# Felderblock_Hebelplatine.net
KiCad netlist of a schematic drawn in EAGLE
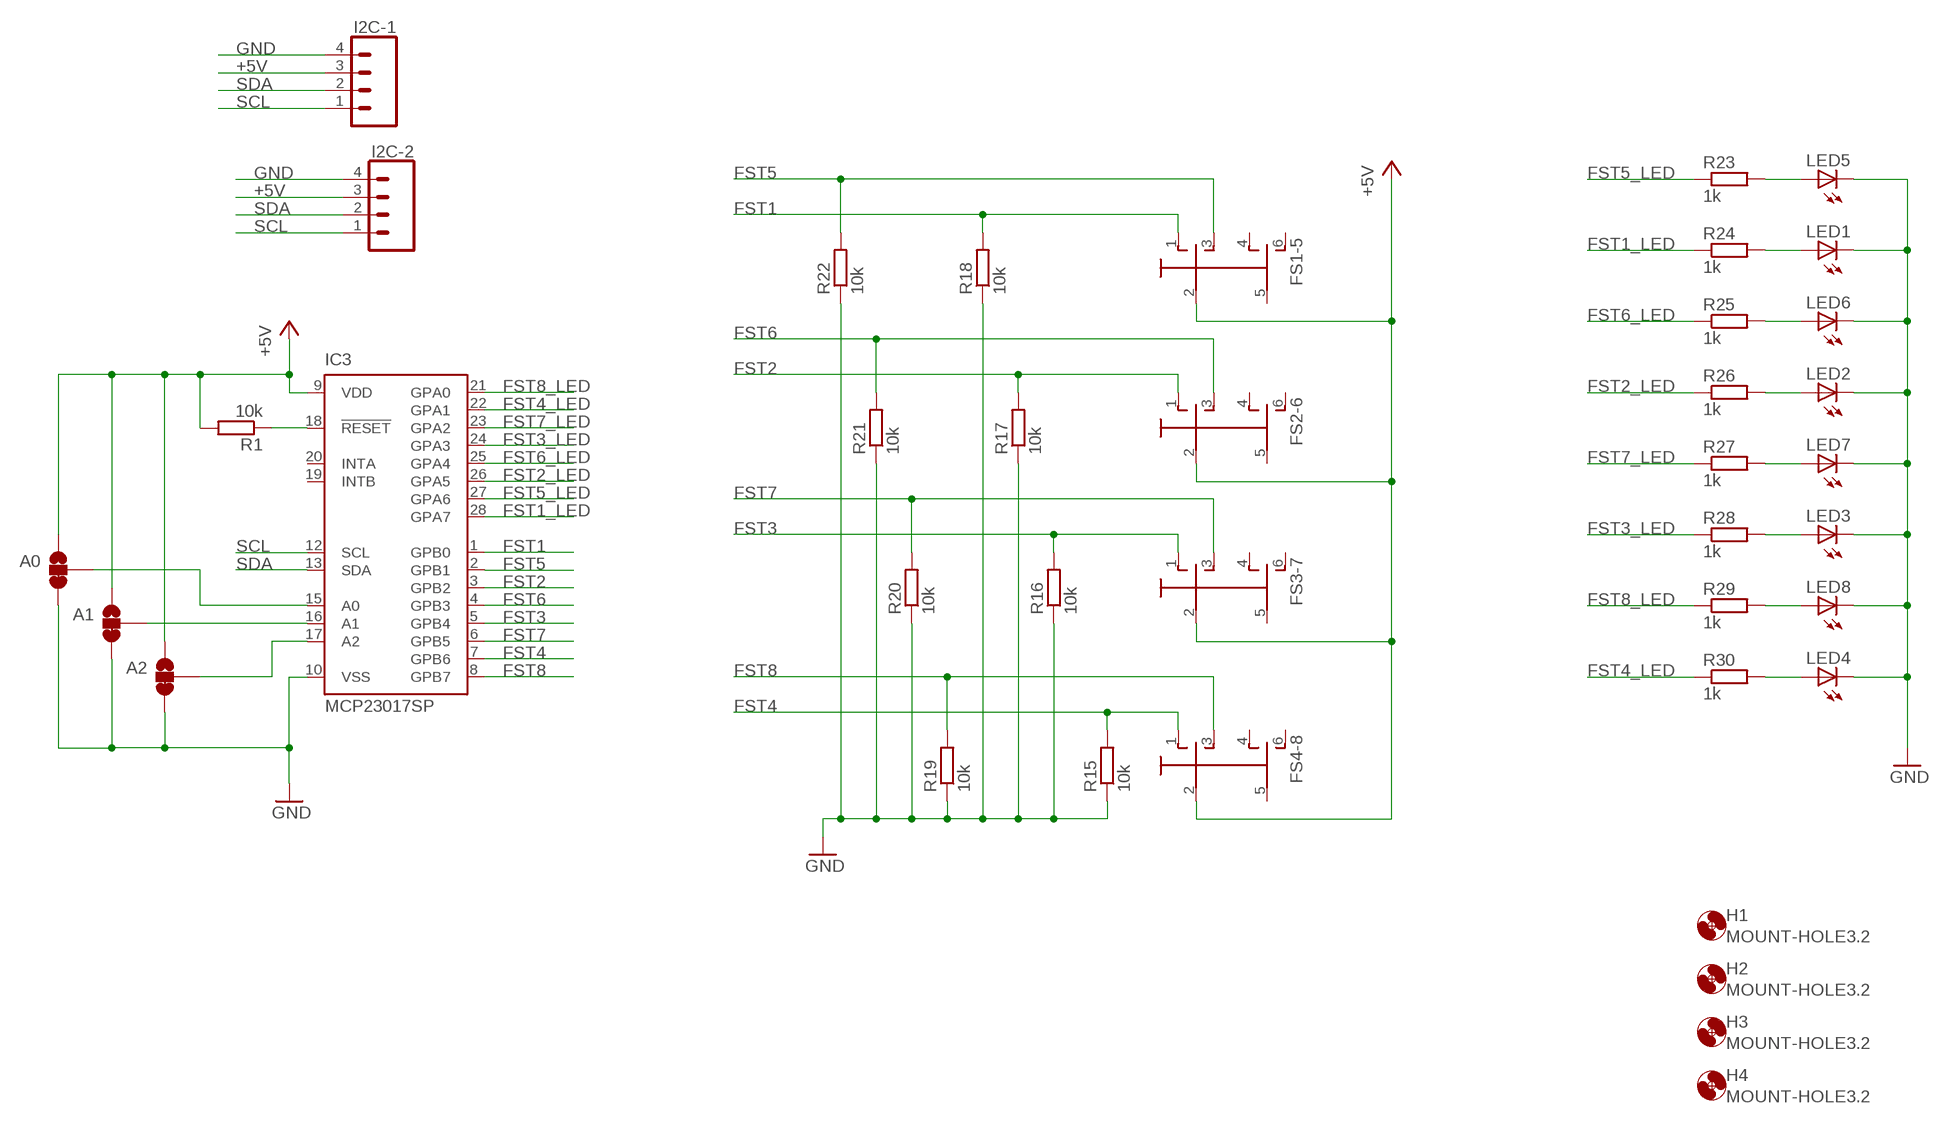
[diagram p0: schematic, sheet 1]

(export (version "E")
  (design (tool "Eeschema 10.0.6"))
  (components
    (comp (ref "A0")
      (value "JUMPER-SMT_3_1-NC_TRACE_SILK")
      (footprint "eagle-import:SMT-JUMPER_3_1-NC_TRACE_SILK")
      (libsource (lib "eagle-import") (part "JUMPER-SMT_3_1-NC_TRACE_SILK"))
    )
    (comp (ref "A1")
      (value "JUMPER-SMT_3_1-NC_TRACE_SILK")
      (footprint "eagle-import:SMT-JUMPER_3_1-NC_TRACE_SILK")
      (libsource (lib "eagle-import") (part "JUMPER-SMT_3_1-NC_TRACE_SILK"))
    )
    (comp (ref "A2")
      (value "JUMPER-SMT_3_1-NC_TRACE_SILK")
      (footprint "eagle-import:SMT-JUMPER_3_1-NC_TRACE_SILK")
      (libsource (lib "eagle-import") (part "JUMPER-SMT_3_1-NC_TRACE_SILK"))
    )
    (comp (ref "FS1-5")
      (value "SW_2POL_ON-OFF-ONSOLDERPAD")
      (footprint "eagle-import:DIL6_LARGE")
      (libsource (lib "eagle-import") (part "SW_2POL_ON-OFF-ONSOLDERPAD"))
    )
    (comp (ref "FS2-6")
      (value "SW_2POL_ON-OFF-ONSOLDERPAD")
      (footprint "eagle-import:DIL6_LARGE")
      (libsource (lib "eagle-import") (part "SW_2POL_ON-OFF-ONSOLDERPAD"))
    )
    (comp (ref "FS3-7")
      (value "SW_2POL_ON-OFF-ONSOLDERPAD")
      (footprint "eagle-import:DIL6_LARGE")
      (libsource (lib "eagle-import") (part "SW_2POL_ON-OFF-ONSOLDERPAD"))
    )
    (comp (ref "FS4-8")
      (value "SW_2POL_ON-OFF-ONSOLDERPAD")
      (footprint "eagle-import:DIL6_LARGE")
      (libsource (lib "eagle-import") (part "SW_2POL_ON-OFF-ONSOLDERPAD"))
    )
    (comp (ref "H1")
      (value "MOUNT-HOLE3.2")
      (footprint "eagle-import:3,2")
      (libsource (lib "eagle-import") (part "MOUNT-HOLE3.2"))
    )
    (comp (ref "H2")
      (value "MOUNT-HOLE3.2")
      (footprint "eagle-import:3,2")
      (libsource (lib "eagle-import") (part "MOUNT-HOLE3.2"))
    )
    (comp (ref "H3")
      (value "MOUNT-HOLE3.2")
      (footprint "eagle-import:3,2")
      (libsource (lib "eagle-import") (part "MOUNT-HOLE3.2"))
    )
    (comp (ref "H4")
      (value "MOUNT-HOLE3.2")
      (footprint "eagle-import:3,2")
      (libsource (lib "eagle-import") (part "MOUNT-HOLE3.2"))
    )
    (comp (ref "I2C-1")
      (value "CONN_04JST-PTH-VERT")
      (footprint "eagle-import:JST-4-PTH-VERT")
      (libsource (lib "eagle-import") (part "CONN_04JST-PTH-VERT"))
    )
    (comp (ref "I2C-2")
      (value "CONN_04JST-PTH-VERT")
      (footprint "eagle-import:JST-4-PTH-VERT")
      (libsource (lib "eagle-import") (part "CONN_04JST-PTH-VERT"))
    )
    (comp (ref "IC3")
      (value "MCP23017SP")
      (footprint "eagle-import:DIL28-3")
      (fields (field (name "MF") "MICROCHIP") (field (name "MPN") "MCP23017-E/SP"))
      (libsource (lib "eagle-import") (part "MCP23017SP"))
    )
    (comp (ref "LED1")
      (value "LED3MM")
      (footprint "eagle-import:LED3MM")
      (libsource (lib "eagle-import") (part "LED3MM"))
    )
    (comp (ref "LED2")
      (value "LED3MM")
      (footprint "eagle-import:LED3MM")
      (libsource (lib "eagle-import") (part "LED3MM"))
    )
    (comp (ref "LED3")
      (value "LED3MM")
      (footprint "eagle-import:LED3MM")
      (libsource (lib "eagle-import") (part "LED3MM"))
    )
    (comp (ref "LED4")
      (value "LED3MM")
      (footprint "eagle-import:LED3MM")
      (libsource (lib "eagle-import") (part "LED3MM"))
    )
    (comp (ref "LED5")
      (value "LED3MM")
      (footprint "eagle-import:LED3MM")
      (libsource (lib "eagle-import") (part "LED3MM"))
    )
    (comp (ref "LED6")
      (value "LED3MM")
      (footprint "eagle-import:LED3MM")
      (libsource (lib "eagle-import") (part "LED3MM"))
    )
    (comp (ref "LED7")
      (value "LED3MM")
      (footprint "eagle-import:LED3MM")
      (libsource (lib "eagle-import") (part "LED3MM"))
    )
    (comp (ref "LED8")
      (value "LED3MM")
      (footprint "eagle-import:LED3MM")
      (libsource (lib "eagle-import") (part "LED3MM"))
    )
    (comp (ref "R1")
      (value "10k")
      (footprint "eagle-import:0207_7")
      (libsource (lib "eagle-import") (part "R-EU_0207/7"))
    )
    (comp (ref "R15")
      (value "10k")
      (footprint "eagle-import:0207_7")
      (libsource (lib "eagle-import") (part "R-EU_0207/7"))
    )
    (comp (ref "R16")
      (value "10k")
      (footprint "eagle-import:0207_7")
      (libsource (lib "eagle-import") (part "R-EU_0207/7"))
    )
    (comp (ref "R17")
      (value "10k")
      (footprint "eagle-import:0207_7")
      (libsource (lib "eagle-import") (part "R-EU_0207/7"))
    )
    (comp (ref "R18")
      (value "10k")
      (footprint "eagle-import:0207_7")
      (libsource (lib "eagle-import") (part "R-EU_0207/7"))
    )
    (comp (ref "R19")
      (value "10k")
      (footprint "eagle-import:0207_7")
      (libsource (lib "eagle-import") (part "R-EU_0207/7"))
    )
    (comp (ref "R20")
      (value "10k")
      (footprint "eagle-import:0207_7")
      (libsource (lib "eagle-import") (part "R-EU_0207/7"))
    )
    (comp (ref "R21")
      (value "10k")
      (footprint "eagle-import:0207_7")
      (libsource (lib "eagle-import") (part "R-EU_0207/7"))
    )
    (comp (ref "R22")
      (value "10k")
      (footprint "eagle-import:0207_7")
      (libsource (lib "eagle-import") (part "R-EU_0207/7"))
    )
    (comp (ref "R23")
      (value "1k")
      (footprint "eagle-import:0207_7")
      (libsource (lib "eagle-import") (part "R-EU_0207/7"))
    )
    (comp (ref "R24")
      (value "1k")
      (footprint "eagle-import:0207_7")
      (libsource (lib "eagle-import") (part "R-EU_0207/7"))
    )
    (comp (ref "R25")
      (value "1k")
      (footprint "eagle-import:0207_7")
      (libsource (lib "eagle-import") (part "R-EU_0207/7"))
    )
    (comp (ref "R26")
      (value "1k")
      (footprint "eagle-import:0207_7")
      (libsource (lib "eagle-import") (part "R-EU_0207/7"))
    )
    (comp (ref "R27")
      (value "1k")
      (footprint "eagle-import:0207_7")
      (libsource (lib "eagle-import") (part "R-EU_0207/7"))
    )
    (comp (ref "R28")
      (value "1k")
      (footprint "eagle-import:0207_7")
      (libsource (lib "eagle-import") (part "R-EU_0207/7"))
    )
    (comp (ref "R29")
      (value "1k")
      (footprint "eagle-import:0207_7")
      (libsource (lib "eagle-import") (part "R-EU_0207/7"))
    )
    (comp (ref "R30")
      (value "1k")
      (footprint "eagle-import:0207_7")
      (libsource (lib "eagle-import") (part "R-EU_0207/7"))
    )
  )
  (nets
    (net (code "1") (name "+5V") (class "Default")
      (node (ref "A0") (pin "1") (pinfunction "1_1") (pintype "passive"))
      (node (ref "A1") (pin "1") (pinfunction "1_1") (pintype "passive"))
      (node (ref "A2") (pin "1") (pinfunction "1_1") (pintype "passive"))
      (node (ref "FS1-5") (pin "2") (pinfunction "P_2") (pintype "passive"))
      (node (ref "FS2-6") (pin "2") (pinfunction "P_2") (pintype "passive"))
      (node (ref "FS3-7") (pin "2") (pinfunction "P_2") (pintype "passive"))
      (node (ref "FS4-8") (pin "2") (pinfunction "P_2") (pintype "passive"))
      (node (ref "I2C-1") (pin "3") (pinfunction "3_3") (pintype "passive"))
      (node (ref "I2C-2") (pin "3") (pinfunction "3_3") (pintype "passive"))
      (node (ref "IC3") (pin "9") (pinfunction "VDD_9") (pintype "power_in"))
      (node (ref "R1") (pin "2") (pinfunction "2_2") (pintype "passive"))
    )
    (net (code "2") (name "/FST1") (class "Default")
      (node (ref "FS1-5") (pin "1") (pinfunction "O_1") (pintype "passive"))
      (node (ref "IC3") (pin "1") (pinfunction "GPB0_1") (pintype "bidirectional"))
      (node (ref "R18") (pin "2") (pinfunction "2_2") (pintype "passive"))
    )
    (net (code "3") (name "/FST1_LED") (class "Default")
      (node (ref "IC3") (pin "28") (pinfunction "GPA7_28") (pintype "bidirectional"))
      (node (ref "R24") (pin "1") (pinfunction "1_1") (pintype "passive"))
    )
    (net (code "4") (name "/FST2") (class "Default")
      (node (ref "FS2-6") (pin "1") (pinfunction "O_1") (pintype "passive"))
      (node (ref "IC3") (pin "3") (pinfunction "GPB2_3") (pintype "bidirectional"))
      (node (ref "R17") (pin "2") (pinfunction "2_2") (pintype "passive"))
    )
    (net (code "5") (name "/FST2_LED") (class "Default")
      (node (ref "IC3") (pin "26") (pinfunction "GPA5_26") (pintype "bidirectional"))
      (node (ref "R26") (pin "1") (pinfunction "1_1") (pintype "passive"))
    )
    (net (code "6") (name "/FST3") (class "Default")
      (node (ref "FS3-7") (pin "1") (pinfunction "O_1") (pintype "passive"))
      (node (ref "IC3") (pin "5") (pinfunction "GPB4_5") (pintype "bidirectional"))
      (node (ref "R16") (pin "2") (pinfunction "2_2") (pintype "passive"))
    )
    (net (code "7") (name "/FST3_LED") (class "Default")
      (node (ref "IC3") (pin "24") (pinfunction "GPA3_24") (pintype "bidirectional"))
      (node (ref "R28") (pin "1") (pinfunction "1_1") (pintype "passive"))
    )
    (net (code "8") (name "/FST4") (class "Default")
      (node (ref "FS4-8") (pin "1") (pinfunction "O_1") (pintype "passive"))
      (node (ref "IC3") (pin "7") (pinfunction "GPB6_7") (pintype "bidirectional"))
      (node (ref "R15") (pin "2") (pinfunction "2_2") (pintype "passive"))
    )
    (net (code "9") (name "/FST4_LED") (class "Default")
      (node (ref "IC3") (pin "22") (pinfunction "GPA1_22") (pintype "bidirectional"))
      (node (ref "R30") (pin "1") (pinfunction "1_1") (pintype "passive"))
    )
    (net (code "10") (name "/FST5") (class "Default")
      (node (ref "FS1-5") (pin "3") (pinfunction "S_3") (pintype "passive"))
      (node (ref "IC3") (pin "2") (pinfunction "GPB1_2") (pintype "bidirectional"))
      (node (ref "R22") (pin "2") (pinfunction "2_2") (pintype "passive"))
    )
    (net (code "11") (name "/FST5_LED") (class "Default")
      (node (ref "IC3") (pin "27") (pinfunction "GPA6_27") (pintype "bidirectional"))
      (node (ref "R23") (pin "1") (pinfunction "1_1") (pintype "passive"))
    )
    (net (code "12") (name "/FST6") (class "Default")
      (node (ref "FS2-6") (pin "3") (pinfunction "S_3") (pintype "passive"))
      (node (ref "IC3") (pin "4") (pinfunction "GPB3_4") (pintype "bidirectional"))
      (node (ref "R21") (pin "2") (pinfunction "2_2") (pintype "passive"))
    )
    (net (code "13") (name "/FST6_LED") (class "Default")
      (node (ref "IC3") (pin "25") (pinfunction "GPA4_25") (pintype "bidirectional"))
      (node (ref "R25") (pin "1") (pinfunction "1_1") (pintype "passive"))
    )
    (net (code "14") (name "/FST7") (class "Default")
      (node (ref "FS3-7") (pin "3") (pinfunction "S_3") (pintype "passive"))
      (node (ref "IC3") (pin "6") (pinfunction "GPB5_6") (pintype "bidirectional"))
      (node (ref "R20") (pin "2") (pinfunction "2_2") (pintype "passive"))
    )
    (net (code "15") (name "/FST7_LED") (class "Default")
      (node (ref "IC3") (pin "23") (pinfunction "GPA2_23") (pintype "bidirectional"))
      (node (ref "R27") (pin "1") (pinfunction "1_1") (pintype "passive"))
    )
    (net (code "16") (name "/FST8") (class "Default")
      (node (ref "FS4-8") (pin "3") (pinfunction "S_3") (pintype "passive"))
      (node (ref "IC3") (pin "8") (pinfunction "GPB7_8") (pintype "bidirectional"))
      (node (ref "R19") (pin "2") (pinfunction "2_2") (pintype "passive"))
    )
    (net (code "17") (name "/FST8_LED") (class "Default")
      (node (ref "IC3") (pin "21") (pinfunction "GPA0_21") (pintype "bidirectional"))
      (node (ref "R29") (pin "1") (pinfunction "1_1") (pintype "passive"))
    )
    (net (code "18") (name "/SCL") (class "Default")
      (node (ref "I2C-1") (pin "1") (pinfunction "1_1") (pintype "passive"))
      (node (ref "I2C-2") (pin "1") (pinfunction "1_1") (pintype "passive"))
      (node (ref "IC3") (pin "12") (pinfunction "SCL_12") (pintype "input"))
    )
    (net (code "19") (name "/SDA") (class "Default")
      (node (ref "I2C-1") (pin "2") (pinfunction "2_2") (pintype "passive"))
      (node (ref "I2C-2") (pin "2") (pinfunction "2_2") (pintype "passive"))
      (node (ref "IC3") (pin "13") (pinfunction "SDA_13") (pintype "bidirectional"))
    )
    (net (code "20") (name "GND") (class "Default")
      (node (ref "A0") (pin "3") (pinfunction "3_3") (pintype "passive"))
      (node (ref "A1") (pin "3") (pinfunction "3_3") (pintype "passive"))
      (node (ref "A2") (pin "3") (pinfunction "3_3") (pintype "passive"))
      (node (ref "I2C-1") (pin "4") (pinfunction "4_4") (pintype "passive"))
      (node (ref "I2C-2") (pin "4") (pinfunction "4_4") (pintype "passive"))
      (node (ref "IC3") (pin "10") (pinfunction "VSS_10") (pintype "power_in"))
      (node (ref "LED1") (pin "K") (pinfunction "C_K") (pintype "passive"))
      (node (ref "LED2") (pin "K") (pinfunction "C_K") (pintype "passive"))
      (node (ref "LED3") (pin "K") (pinfunction "C_K") (pintype "passive"))
      (node (ref "LED4") (pin "K") (pinfunction "C_K") (pintype "passive"))
      (node (ref "LED5") (pin "K") (pinfunction "C_K") (pintype "passive"))
      (node (ref "LED6") (pin "K") (pinfunction "C_K") (pintype "passive"))
      (node (ref "LED7") (pin "K") (pinfunction "C_K") (pintype "passive"))
      (node (ref "LED8") (pin "K") (pinfunction "C_K") (pintype "passive"))
      (node (ref "R15") (pin "1") (pinfunction "1_1") (pintype "passive"))
      (node (ref "R16") (pin "1") (pinfunction "1_1") (pintype "passive"))
      (node (ref "R17") (pin "1") (pinfunction "1_1") (pintype "passive"))
      (node (ref "R18") (pin "1") (pinfunction "1_1") (pintype "passive"))
      (node (ref "R19") (pin "1") (pinfunction "1_1") (pintype "passive"))
      (node (ref "R20") (pin "1") (pinfunction "1_1") (pintype "passive"))
      (node (ref "R21") (pin "1") (pinfunction "1_1") (pintype "passive"))
      (node (ref "R22") (pin "1") (pinfunction "1_1") (pintype "passive"))
    )
    (net (code "21") (name "Net-(IC3-A0)") (class "Default")
      (node (ref "A0") (pin "2") (pinfunction "2_2") (pintype "passive"))
      (node (ref "IC3") (pin "15") (pinfunction "A0_15") (pintype "input"))
    )
    (net (code "22") (name "Net-(IC3-A1)") (class "Default")
      (node (ref "A1") (pin "2") (pinfunction "2_2") (pintype "passive"))
      (node (ref "IC3") (pin "16") (pinfunction "A1_16") (pintype "input"))
    )
    (net (code "23") (name "Net-(IC3-A2)") (class "Default")
      (node (ref "A2") (pin "2") (pinfunction "2_2") (pintype "passive"))
      (node (ref "IC3") (pin "17") (pinfunction "A2_17") (pintype "input"))
    )
    (net (code "24") (name "Net-(IC3-~{RESET})") (class "Default")
      (node (ref "IC3") (pin "18") (pinfunction "~{RESET}_18") (pintype "input"))
      (node (ref "R1") (pin "1") (pinfunction "1_1") (pintype "passive"))
    )
    (net (code "25") (name "Net-(LED1-PadA)") (class "Default")
      (node (ref "LED1") (pin "A") (pinfunction "A_A") (pintype "passive"))
      (node (ref "R24") (pin "2") (pinfunction "2_2") (pintype "passive"))
    )
    (net (code "26") (name "Net-(LED2-PadA)") (class "Default")
      (node (ref "LED2") (pin "A") (pinfunction "A_A") (pintype "passive"))
      (node (ref "R26") (pin "2") (pinfunction "2_2") (pintype "passive"))
    )
    (net (code "27") (name "Net-(LED3-PadA)") (class "Default")
      (node (ref "LED3") (pin "A") (pinfunction "A_A") (pintype "passive"))
      (node (ref "R28") (pin "2") (pinfunction "2_2") (pintype "passive"))
    )
    (net (code "28") (name "Net-(LED4-PadA)") (class "Default")
      (node (ref "LED4") (pin "A") (pinfunction "A_A") (pintype "passive"))
      (node (ref "R30") (pin "2") (pinfunction "2_2") (pintype "passive"))
    )
    (net (code "29") (name "Net-(LED5-PadA)") (class "Default")
      (node (ref "LED5") (pin "A") (pinfunction "A_A") (pintype "passive"))
      (node (ref "R23") (pin "2") (pinfunction "2_2") (pintype "passive"))
    )
    (net (code "30") (name "Net-(LED6-PadA)") (class "Default")
      (node (ref "LED6") (pin "A") (pinfunction "A_A") (pintype "passive"))
      (node (ref "R25") (pin "2") (pinfunction "2_2") (pintype "passive"))
    )
    (net (code "31") (name "Net-(LED7-PadA)") (class "Default")
      (node (ref "LED7") (pin "A") (pinfunction "A_A") (pintype "passive"))
      (node (ref "R27") (pin "2") (pinfunction "2_2") (pintype "passive"))
    )
    (net (code "32") (name "Net-(LED8-PadA)") (class "Default")
      (node (ref "LED8") (pin "A") (pinfunction "A_A") (pintype "passive"))
      (node (ref "R29") (pin "2") (pinfunction "2_2") (pintype "passive"))
    )
    (net (code "33") (name "unconnected-(FS1-5-O1-Pad4)") (class "Default")
      (node (ref "FS1-5") (pin "4") (pinfunction "O1_4") (pintype "passive"))
    )
    (net (code "34") (name "unconnected-(FS1-5-P1-Pad5)") (class "Default")
      (node (ref "FS1-5") (pin "5") (pinfunction "P1_5") (pintype "passive"))
    )
    (net (code "35") (name "unconnected-(FS1-5-S1-Pad6)") (class "Default")
      (node (ref "FS1-5") (pin "6") (pinfunction "S1_6") (pintype "passive"))
    )
    (net (code "36") (name "unconnected-(FS2-6-O1-Pad4)") (class "Default")
      (node (ref "FS2-6") (pin "4") (pinfunction "O1_4") (pintype "passive"))
    )
    (net (code "37") (name "unconnected-(FS2-6-P1-Pad5)") (class "Default")
      (node (ref "FS2-6") (pin "5") (pinfunction "P1_5") (pintype "passive"))
    )
    (net (code "38") (name "unconnected-(FS2-6-S1-Pad6)") (class "Default")
      (node (ref "FS2-6") (pin "6") (pinfunction "S1_6") (pintype "passive"))
    )
    (net (code "39") (name "unconnected-(FS3-7-O1-Pad4)") (class "Default")
      (node (ref "FS3-7") (pin "4") (pinfunction "O1_4") (pintype "passive"))
    )
    (net (code "40") (name "unconnected-(FS3-7-P1-Pad5)") (class "Default")
      (node (ref "FS3-7") (pin "5") (pinfunction "P1_5") (pintype "passive"))
    )
    (net (code "41") (name "unconnected-(FS3-7-S1-Pad6)") (class "Default")
      (node (ref "FS3-7") (pin "6") (pinfunction "S1_6") (pintype "passive"))
    )
    (net (code "42") (name "unconnected-(FS4-8-O1-Pad4)") (class "Default")
      (node (ref "FS4-8") (pin "4") (pinfunction "O1_4") (pintype "passive"))
    )
    (net (code "43") (name "unconnected-(FS4-8-P1-Pad5)") (class "Default")
      (node (ref "FS4-8") (pin "5") (pinfunction "P1_5") (pintype "passive"))
    )
    (net (code "44") (name "unconnected-(FS4-8-S1-Pad6)") (class "Default")
      (node (ref "FS4-8") (pin "6") (pinfunction "S1_6") (pintype "passive"))
    )
    (net (code "45") (name "unconnected-(IC3-INTA-Pad20)") (class "Default")
      (node (ref "IC3") (pin "20") (pinfunction "INTA_20") (pintype "output"))
    )
    (net (code "46") (name "unconnected-(IC3-INTB-Pad19)") (class "Default")
      (node (ref "IC3") (pin "19") (pinfunction "INTB_19") (pintype "output"))
    )
  )
)
